# Isolation.net
KiCad netlist of a schematic drawn in Altium Designer
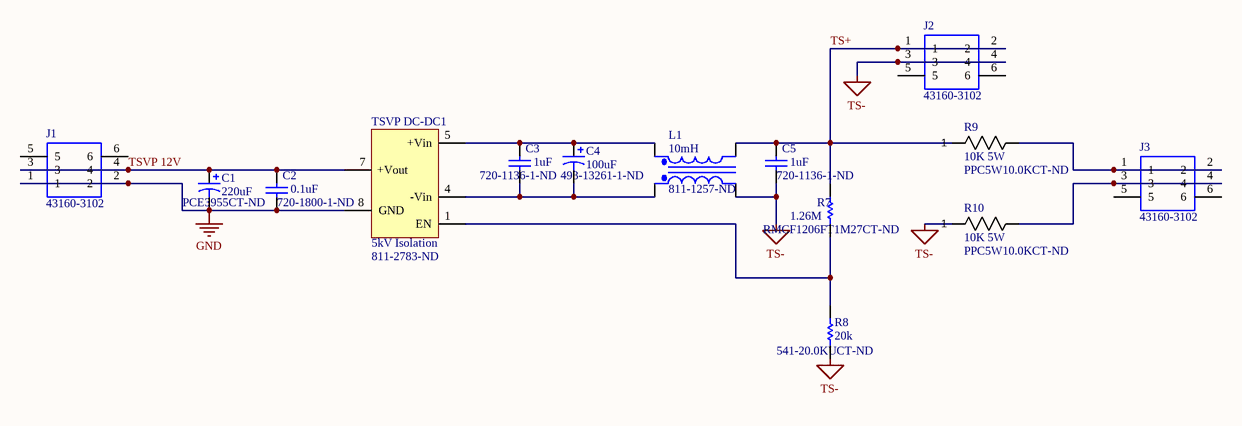
[diagram p0: Isolation.SchDoc]

(export (version "E")
  (design (tool "Eeschema 10.0.6"))
  (components
    (comp (ref "C1")
      (value "220uF")
      (footprint "EEE-1VA221UP")
      (description "Panasonic Electrolytic 35V, 20% EEE-1VA221UP")
      (fields (field (name "SUPPLIER PART NUMBER 1") "PCE3955CT-ND"))
      (libsource (lib "Isolation") (part "Cap Pol1"))
    )
    (comp (ref "C2")
      (value "0.1uF")
      (footprint "C1206")
      (description "C0603C104K3RACTU")
      (fields
        (field (name "SUPPLIER PART NUMBER 1") "720-1800-1-ND")
        (field (name "Comment") "C0603")
        (field (name "PUBLISHER") "Altium Limited")
      )
      (libsource (lib "Isolation") (part "C0603"))
    )
    (comp (ref "C3")
      (value "1uF")
      (footprint "2225 Package")
      (description "C0603C104K3RACTU")
      (fields
        (field (name "SUPPLIER PART NUMBER 1") "720-1136-1-ND")
        (field (name "Comment") "C0603")
        (field (name "PUBLISHER") "Altium Limited")
      )
      (libsource (lib "Isolation") (part "C0603_1"))
    )
    (comp (ref "C4")
      (value "100uF")
      (footprint "NichiconCAP")
      (description "Nichicon 200V 100uF TH Capacitor  UCA2D101MHD6TN")
      (fields (field (name "SUPPLIER PART NUMBER 1") "493-13261-1-ND"))
      (libsource (lib "Isolation") (part "Cap Pol1_1"))
    )
    (comp (ref "C5")
      (value "1uF")
      (footprint "2225 Package")
      (description "C0603C104K3RACTU")
      (fields
        (field (name "SUPPLIER PART NUMBER 1") "720-1136-1-ND")
        (field (name "Comment") "C0603")
        (field (name "PUBLISHER") "Altium Limited")
      )
      (libsource (lib "Isolation") (part "C0603_1"))
    )
    (comp (ref "J1")
      (value "43160-3102")
      (footprint "431603102")
      (fields (field (name "RS PART NUMBER") "3639982P"))
      (libsource (lib "Isolation") (part "43160-3102"))
    )
    (comp (ref "J2")
      (value "43160-3102")
      (footprint "431603102")
      (fields (field (name "RS PART NUMBER") "3639982P"))
      (libsource (lib "Isolation") (part "43160-3102"))
    )
    (comp (ref "J3")
      (value "43160-3102")
      (footprint "431603102")
      (fields (field (name "RS PART NUMBER") "3639982P"))
      (libsource (lib "Isolation") (part "43160-3102"))
    )
    (comp (ref "L1")
      (value "10mH")
      (footprint "52106C")
      (description "MuRata 52106C Common Choke")
      (fields
        (field (name "SUPPLIER PART NUMBER 1") "811-1257-ND")
        (field (name "PUBLISHER") "Altium Limited")
      )
      (libsource (lib "Isolation") (part "Trans Ideal"))
    )
    (comp (ref "R7")
      (value "1.26M")
      (footprint "C1206")
      (description "Resistor")
      (fields
        (field (name "SUPPLIER PART NUMBER 1") "RMCF1206FT1M27CT-ND")
        (field (name "Comment") "Res1")
        (field (name "PUBLISHER") "Altium Limited")
      )
      (libsource (lib "Isolation") (part "Res1"))
    )
    (comp (ref "R8")
      (value "20k")
      (footprint "C1206")
      (description "Precision Thick Film Chip Resistor, 10 Ohm to 2.2M Ohm Range, 1% Tolerance, 0805 Size, 0.1 W")
      (fields
        (field (name "SUPPLIER PART NUMBER 1") "541-20.0KUCT-ND")
        (field (name "PUBLISHER") "Altium Limited")
      )
      (libsource (lib "Isolation") (part "ERJ6EN"))
    )
    (comp (ref "R9")
      (value "10K 5W")
      (footprint "Res THRU Hole 10k 5W")
      (fields (field (name "SUPPLIER PART NUMBER 1") "PPC5W10.0KCT-ND"))
      (libsource (lib "Isolation") (part "Resistor 10kOhm 5W"))
    )
    (comp (ref "R10")
      (value "10K 5W")
      (footprint "Res THRU Hole 10k 5W")
      (fields (field (name "SUPPLIER PART NUMBER 1") "PPC5W10.0KCT-ND"))
      (libsource (lib "Isolation") (part "Resistor 10kOhm 5W"))
    )
    (comp (ref "TSVP DC-DC1")
      (value "RUW15SL 12C")
      (footprint "RUW15SL 12C")
      (fields (field (name "NOTE") "5kV Isolation") (field (name "SUPPLIER PART NUMBER 1") "811-2783-ND"))
      (libsource (lib "Isolation") (part "RUW15SL 12C"))
    )
  )
  (nets
    (net (code "1") (name "/TS+") (class "Default")
      (node (ref "C5") (pin "2") (pinfunction "2_2") (pintype "passive"))
      (node (ref "J2") (pin "1") (pinfunction "1_1") (pintype "passive"))
      (node (ref "J2") (pin "2") (pinfunction "2_2") (pintype "passive"))
      (node (ref "L1") (pin "3") (pintype "passive"))
      (node (ref "R7") (pin "2") (pinfunction "2_2") (pintype "passive"))
      (node (ref "R9") (pin "1") (pinfunction "1_1") (pintype "passive"))
    )
    (net (code "2") (name "/TSVP 12V") (class "Default")
      (node (ref "C1") (pin "1") (pinfunction "1_1") (pintype "passive"))
      (node (ref "C2") (pin "2") (pinfunction "2_2") (pintype "passive"))
      (node (ref "J1") (pin "3") (pinfunction "3_3") (pintype "passive"))
      (node (ref "J1") (pin "4") (pinfunction "4_4") (pintype "passive"))
      (node (ref "TSVP DC-DC1") (pin "7") (pinfunction "+Vout_7") (pintype "passive"))
    )
    (net (code "3") (name "GND") (class "Default")
      (node (ref "C1") (pin "2") (pinfunction "2_2") (pintype "passive"))
      (node (ref "C2") (pin "1") (pinfunction "1_1") (pintype "passive"))
      (node (ref "J1") (pin "1") (pinfunction "1_1") (pintype "passive"))
      (node (ref "J1") (pin "2") (pinfunction "2_2") (pintype "passive"))
      (node (ref "TSVP DC-DC1") (pin "8") (pinfunction "GND_8") (pintype "passive"))
    )
    (net (code "4") (name "Net-(J3-Pad1)") (class "Default")
      (node (ref "J3") (pin "1") (pinfunction "1_1") (pintype "passive"))
      (node (ref "J3") (pin "2") (pinfunction "2_2") (pintype "passive"))
      (node (ref "R9") (pin "2") (pinfunction "2_2") (pintype "passive"))
    )
    (net (code "5") (name "Net-(J3-Pad3)") (class "Default")
      (node (ref "J3") (pin "3") (pinfunction "3_3") (pintype "passive"))
      (node (ref "J3") (pin "4") (pinfunction "4_4") (pintype "passive"))
      (node (ref "R10") (pin "2") (pinfunction "2_2") (pintype "passive"))
    )
    (net (code "6") (name "Net-(TSVP DC-DC1-+Vin)") (class "Default")
      (node (ref "C3") (pin "2") (pinfunction "2_2") (pintype "passive"))
      (node (ref "C4") (pin "1") (pinfunction "1_1") (pintype "passive"))
      (node (ref "L1") (pin "2") (pintype "passive"))
      (node (ref "TSVP DC-DC1") (pin "5") (pinfunction "+Vin_5") (pintype "passive"))
    )
    (net (code "7") (name "Net-(TSVP DC-DC1--Vin)") (class "Default")
      (node (ref "C3") (pin "1") (pinfunction "1_1") (pintype "passive"))
      (node (ref "C4") (pin "2") (pinfunction "2_2") (pintype "passive"))
      (node (ref "L1") (pin "1") (pintype "passive"))
      (node (ref "TSVP DC-DC1") (pin "4") (pinfunction "-Vin_4") (pintype "passive"))
    )
    (net (code "8") (name "Net-(TSVP DC-DC1-EN)") (class "Default")
      (node (ref "R7") (pin "1") (pinfunction "1_1") (pintype "passive"))
      (node (ref "R8") (pin "2") (pinfunction "2_2") (pintype "passive"))
      (node (ref "TSVP DC-DC1") (pin "1") (pinfunction "EN_1") (pintype "passive"))
    )
    (net (code "9") (name "TS-") (class "Default")
      (node (ref "C5") (pin "1") (pinfunction "1_1") (pintype "passive"))
      (node (ref "J2") (pin "3") (pinfunction "3_3") (pintype "passive"))
      (node (ref "J2") (pin "4") (pinfunction "4_4") (pintype "passive"))
      (node (ref "L1") (pin "4") (pintype "passive"))
      (node (ref "R10") (pin "1") (pinfunction "1_1") (pintype "passive"))
      (node (ref "R8") (pin "1") (pinfunction "1_1") (pintype "passive"))
    )
    (net (code "10") (name "unconnected-(J1-Pad5)") (class "Default")
      (node (ref "J1") (pin "5") (pinfunction "5_5") (pintype "passive"))
    )
    (net (code "11") (name "unconnected-(J1-Pad6)") (class "Default")
      (node (ref "J1") (pin "6") (pinfunction "6_6") (pintype "passive"))
    )
    (net (code "12") (name "unconnected-(J2-Pad5)") (class "Default")
      (node (ref "J2") (pin "5") (pinfunction "5_5") (pintype "passive"))
    )
    (net (code "13") (name "unconnected-(J2-Pad6)") (class "Default")
      (node (ref "J2") (pin "6") (pinfunction "6_6") (pintype "passive"))
    )
    (net (code "14") (name "unconnected-(J3-Pad5)") (class "Default")
      (node (ref "J3") (pin "5") (pinfunction "5_5") (pintype "passive"))
    )
    (net (code "15") (name "unconnected-(J3-Pad6)") (class "Default")
      (node (ref "J3") (pin "6") (pinfunction "6_6") (pintype "passive"))
    )
  )
)
